# OV_OC.net
KiCad netlist of a schematic drawn in Altium Designer
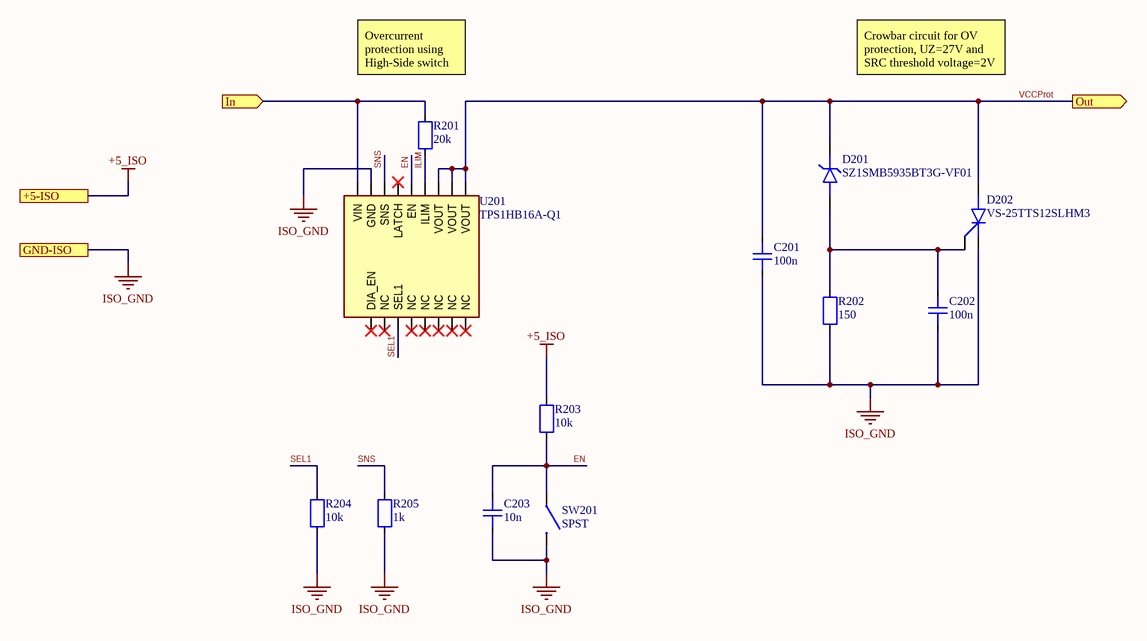
[diagram p0: OV_OC.SchDoc]

(export (version "E")
  (design (tool "Eeschema 10.0.6"))
  (components
    (comp (ref "C201")
      (value "100n")
      (footprint "CAP0603")
      (libsource (lib "schematic_library") (part "Capacitor"))
    )
    (comp (ref "C202")
      (value "100n")
      (footprint "CAP0603")
      (libsource (lib "schematic_library") (part "Capacitor"))
    )
    (comp (ref "C203")
      (value "10n")
      (footprint "CAP0603")
      (libsource (lib "schematic_library") (part "Capacitor"))
    )
    (comp (ref "D201")
      (value "SZ1SMB5935BT3G-VF01")
      (footprint "DIOM5334X23N")
      (libsource (lib "schematic_library") (part "Zener"))
    )
    (comp (ref "D202")
      (value "VS-25TTS12SLHM3")
      (footprint "DPAK254P1524X483-3N")
      (description "Thyristor, Surface Mount, Phase Control SCR, 16 A")
      (libsource (lib "schematic_library") (part "VS-25TTS12SLHM3"))
    )
    (comp (ref "R201")
      (value "20k")
      (footprint "RES0603")
      (libsource (lib "schematic_library") (part "Resistor"))
    )
    (comp (ref "R202")
      (value "150")
      (footprint "RES0603")
      (libsource (lib "schematic_library") (part "Resistor"))
    )
    (comp (ref "R203")
      (value "10k")
      (footprint "RES0603")
      (libsource (lib "schematic_library") (part "Resistor"))
    )
    (comp (ref "R204")
      (value "10k")
      (footprint "RES0603")
      (libsource (lib "schematic_library") (part "Resistor"))
    )
    (comp (ref "R205")
      (value "1k")
      (footprint "RES0603")
      (libsource (lib "schematic_library") (part "Resistor"))
    )
    (comp (ref "SW201")
      (value "SPST")
      (footprint "SPSTSW")
      (description "SPST 24VDC switch")
      (libsource (lib "schematic_library") (part "1DS04-254-2-01BK-SMT"))
    )
    (comp (ref "U201")
      (value "TPS1HB16A-Q1")
      (footprint "TSOP65P640X120_HS-17N")
      (description "40-V, 16-mΩ, 1-ch automotive smart high-side switch with adjustable current limit")
      (libsource (lib "schematic_library") (part "TPS1HB16A-Q1"))
    )
  )
  (nets
    (net (code "1") (name "+5_ISO") (class "Default") (node (ref "R203") (pin "1") (pintype "passive")))
    (net (code "2") (name "/EN") (class "Default")
      (node (ref "C203") (pin "1") (pintype "passive"))
      (node (ref "R203") (pin "2") (pintype "passive"))
      (node (ref "SW201") (pin "1") (pintype "passive"))
      (node (ref "U201") (pin "4") (pinfunction "EN_4") (pintype "passive"))
    )
    (net (code "3") (name "/ILIM") (class "Default")
      (node (ref "R201") (pin "2") (pintype "passive"))
      (node (ref "U201") (pin "5") (pinfunction "ILIM_5") (pintype "passive"))
    )
    (net (code "4") (name "/In") (class "Default")
      (node (ref "R201") (pin "1") (pintype "passive"))
      (node (ref "U201") (pin "17") (pinfunction "VIN_17") (pintype "passive"))
    )
    (net (code "5") (name "/SEL1") (class "Default")
      (node (ref "R204") (pin "1") (pintype "passive"))
      (node (ref "U201") (pin "14") (pinfunction "SEL1_14") (pintype "passive"))
    )
    (net (code "6") (name "/SNS") (class "Default")
      (node (ref "R205") (pin "1") (pintype "passive"))
      (node (ref "U201") (pin "2") (pinfunction "SNS_2") (pintype "passive"))
    )
    (net (code "7") (name "/VCCProt") (class "Default")
      (node (ref "C201") (pin "1") (pintype "passive"))
      (node (ref "D201") (pin "1") (pinfunction "Cathode_1") (pintype "passive"))
      (node (ref "D202") (pin "4") (pinfunction "Anode_4") (pintype "passive"))
      (node (ref "U201") (pin "6") (pinfunction "VOUT_6") (pintype "passive"))
      (node (ref "U201") (pin "7") (pinfunction "VOUT_7") (pintype "passive"))
      (node (ref "U201") (pin "8") (pinfunction "VOUT_8") (pintype "passive"))
    )
    (net (code "8") (name "ISO_GND") (class "Default")
      (node (ref "C201") (pin "2") (pintype "passive"))
      (node (ref "C202") (pin "2") (pintype "passive"))
      (node (ref "C203") (pin "2") (pintype "passive"))
      (node (ref "D202") (pin "1") (pinfunction "Cathode_1") (pintype "passive"))
      (node (ref "R202") (pin "2") (pintype "passive"))
      (node (ref "R204") (pin "2") (pintype "passive"))
      (node (ref "R205") (pin "2") (pintype "passive"))
      (node (ref "SW201") (pin "2") (pintype "passive"))
      (node (ref "U201") (pin "1") (pinfunction "GND_1") (pintype "passive"))
    )
    (net (code "9") (name "Net-(D201-Anode)") (class "Default")
      (node (ref "C202") (pin "1") (pintype "passive"))
      (node (ref "D201") (pin "2") (pinfunction "Anode_2") (pintype "passive"))
      (node (ref "D202") (pin "3") (pinfunction "Gate_3") (pintype "passive"))
      (node (ref "R202") (pin "1") (pintype "passive"))
    )
    (net (code "10") (name "unconnected-(U201-DIA_EN-Pad16)") (class "Default")
      (node (ref "U201") (pin "16") (pinfunction "DIA_EN_16") (pintype "passive+no_connect"))
    )
    (net (code "11") (name "unconnected-(U201-LATCH-Pad3)") (class "Default")
      (node (ref "U201") (pin "3") (pinfunction "LATCH_3") (pintype "passive+no_connect"))
    )
    (net (code "12") (name "unconnected-(U201-NC-Pad9)") (class "Default")
      (node (ref "U201") (pin "9") (pinfunction "NC_9") (pintype "passive+no_connect"))
    )
    (net (code "13") (name "unconnected-(U201-NC-Pad10)") (class "Default")
      (node (ref "U201") (pin "10") (pinfunction "NC_10") (pintype "passive+no_connect"))
    )
    (net (code "14") (name "unconnected-(U201-NC-Pad11)") (class "Default")
      (node (ref "U201") (pin "11") (pinfunction "NC_11") (pintype "passive+no_connect"))
    )
    (net (code "15") (name "unconnected-(U201-NC-Pad12)") (class "Default")
      (node (ref "U201") (pin "12") (pinfunction "NC_12") (pintype "passive+no_connect"))
    )
    (net (code "16") (name "unconnected-(U201-NC-Pad13)") (class "Default")
      (node (ref "U201") (pin "13") (pinfunction "NC_13") (pintype "passive+no_connect"))
    )
    (net (code "17") (name "unconnected-(U201-NC-Pad15)") (class "Default")
      (node (ref "U201") (pin "15") (pinfunction "NC_15") (pintype "passive+no_connect"))
    )
  )
)
